# LIH.net
KiCad netlist of a schematic drawn in EAGLE
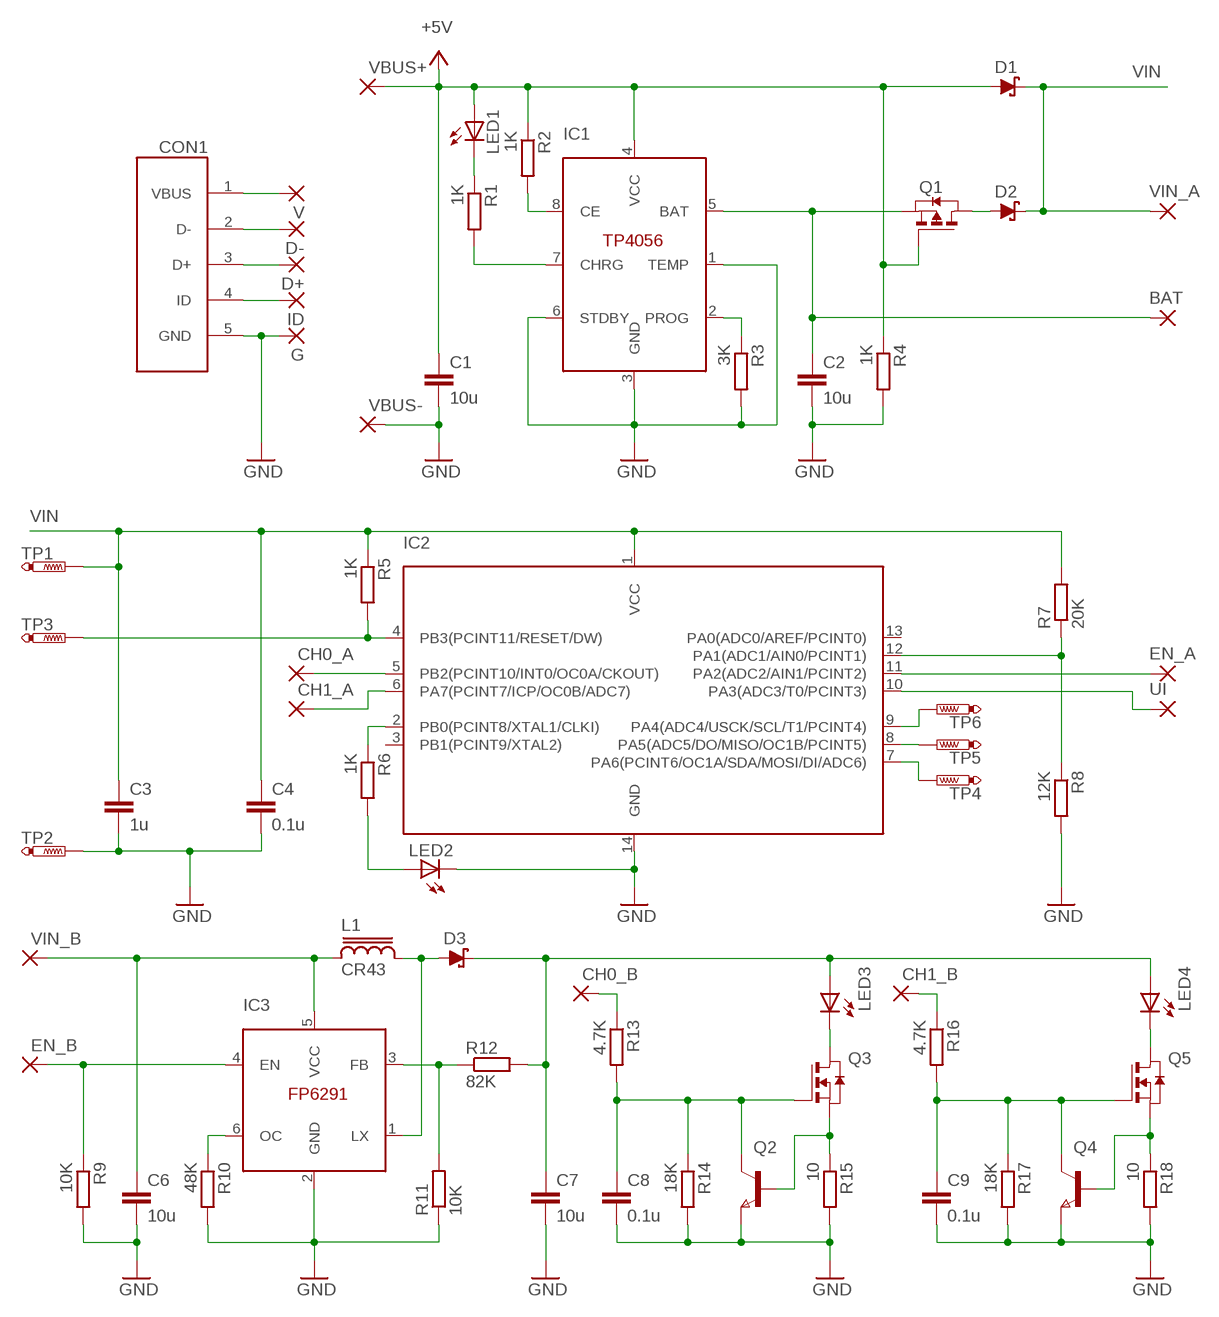
[diagram p0: schematic, sheet 1]

(export (version "E")
  (design (tool "Eeschema 10.0.6"))
  (components
    (comp (ref "BAT")
      (value "WIREPADSMD1,27-254")
      (footprint "eagle-import:1,6_0,8")
      (libsource (lib "eagle-import") (part "1,6/0,8"))
    )
    (comp (ref "C1")
      (value "10u")
      (footprint "eagle-import:C0805K")
      (libsource (lib "eagle-import") (part "C-EUC0805K"))
    )
    (comp (ref "C2")
      (value "10u")
      (footprint "eagle-import:C0805K")
      (libsource (lib "eagle-import") (part "C-EUC0805K"))
    )
    (comp (ref "C3")
      (value "1u")
      (footprint "eagle-import:C0805K")
      (libsource (lib "eagle-import") (part "C-EUC0805K"))
    )
    (comp (ref "C4")
      (value "0.1u")
      (footprint "eagle-import:C0805K")
      (libsource (lib "eagle-import") (part "C-EUC0805K"))
    )
    (comp (ref "C6")
      (value "10u")
      (footprint "eagle-import:C0805K")
      (libsource (lib "eagle-import") (part "C-EUC0805K"))
    )
    (comp (ref "C7")
      (value "10u")
      (footprint "eagle-import:C0805K")
      (libsource (lib "eagle-import") (part "C-EUC0805K"))
    )
    (comp (ref "C8")
      (value "0.1u")
      (footprint "eagle-import:C0805K")
      (libsource (lib "eagle-import") (part "C-EUC0805K"))
    )
    (comp (ref "C9")
      (value "0.1u")
      (footprint "eagle-import:C0805K")
      (libsource (lib "eagle-import") (part "C-EUC0805K"))
    )
    (comp (ref "CH0_A")
      (value "1,6/0,8")
      (footprint "eagle-import:1,6_0,8")
      (libsource (lib "eagle-import") (part "1,6/0,8"))
    )
    (comp (ref "CH0_B")
      (value "1,6/0,8")
      (footprint "eagle-import:1,6_0,8")
      (libsource (lib "eagle-import") (part "1,6/0,8"))
    )
    (comp (ref "CH1_A")
      (value "1,6/0,8")
      (footprint "eagle-import:1,6_0,8")
      (libsource (lib "eagle-import") (part "1,6/0,8"))
    )
    (comp (ref "CH1_B")
      (value "1,6/0,8")
      (footprint "eagle-import:1,6_0,8")
      (libsource (lib "eagle-import") (part "1,6/0,8"))
    )
    (comp (ref "CON1")
      (value "MK5P")
      (footprint "eagle-import:MK5P")
      (libsource (lib "eagle-import") (part "MK5P"))
    )
    (comp (ref "D+")
      (value "SMD2")
      (footprint "eagle-import:SMD1,27-2,54")
      (libsource (lib "eagle-import") (part "SMD2"))
    )
    (comp (ref "D-")
      (value "SMD2")
      (footprint "eagle-import:SMD1,27-2,54")
      (libsource (lib "eagle-import") (part "SMD2"))
    )
    (comp (ref "D1")
      (value "SCHOTTKYSCHOTTKY-DO214AC")
      (footprint "eagle-import:DO214AC")
      (libsource (lib "eagle-import") (part "SCHOTTKYSCHOTTKY-DO214AC"))
    )
    (comp (ref "D2")
      (value "SCHOTTKYSCHOTTKY-DO214AC")
      (footprint "eagle-import:DO214AC")
      (libsource (lib "eagle-import") (part "SCHOTTKYSCHOTTKY-DO214AC"))
    )
    (comp (ref "D3")
      (value "SCHOTTKYSCHOTTKY-DO214AC")
      (footprint "eagle-import:DO214AC")
      (libsource (lib "eagle-import") (part "SCHOTTKYSCHOTTKY-DO214AC"))
    )
    (comp (ref "EN_A")
      (value "WIREPADSMD1,27-254")
      (footprint "eagle-import:1,6_0,8")
      (libsource (lib "eagle-import") (part "1,6/0,8"))
    )
    (comp (ref "EN_B")
      (value "WIREPADSMD1,27-254")
      (footprint "eagle-import:1,6_0,8")
      (libsource (lib "eagle-import") (part "1,6/0,8"))
    )
    (comp (ref "G")
      (value "SMD2")
      (footprint "eagle-import:SMD1,27-2,54")
      (libsource (lib "eagle-import") (part "SMD2"))
    )
    (comp (ref "IC1")
      (value "TP4056")
      (footprint "eagle-import:SO8")
      (libsource (lib "eagle-import") (part "TP4056"))
    )
    (comp (ref "IC2")
      (value "ATTINY24A")
      (footprint "eagle-import:SO14")
      (libsource (lib "eagle-import") (part "ATTINY24A"))
    )
    (comp (ref "IC3")
      (value "FP6291")
      (footprint "eagle-import:SOT-23-6")
      (libsource (lib "eagle-import") (part "FP6291"))
    )
    (comp (ref "ID")
      (value "SMD2")
      (footprint "eagle-import:SMD1,27-2,54")
      (libsource (lib "eagle-import") (part "SMD2"))
    )
    (comp (ref "L1")
      (value "CR43")
      (footprint "eagle-import:CR43")
      (libsource (lib "eagle-import") (part "CR43"))
    )
    (comp (ref "LED1")
      (value "LEDSML0805")
      (footprint "eagle-import:SML0805")
      (libsource (lib "eagle-import") (part "LEDSML0805"))
    )
    (comp (ref "LED2")
      (value "LEDSML0805")
      (footprint "eagle-import:SML0805")
      (libsource (lib "eagle-import") (part "LEDSML0805"))
    )
    (comp (ref "LED3")
      (value "2835")
      (footprint "eagle-import:2835")
      (libsource (lib "eagle-import") (part "2835"))
    )
    (comp (ref "LED4")
      (value "2835")
      (footprint "eagle-import:2835")
      (libsource (lib "eagle-import") (part "2835"))
    )
    (comp (ref "Q1")
      (value "PMOSSOT23")
      (footprint "eagle-import:SOT-23")
      (libsource (lib "eagle-import") (part "PMOSSOT23"))
    )
    (comp (ref "Q2")
      (value "NPNSOT23")
      (footprint "eagle-import:SOT-23")
      (fields (field (name "MPN") "DSS20201L-7"))
      (libsource (lib "eagle-import") (part "NPNSOT23"))
    )
    (comp (ref "Q3")
      (value "NMOSSOT23")
      (footprint "eagle-import:SOT-23")
      (libsource (lib "eagle-import") (part "NMOSSOT23"))
    )
    (comp (ref "Q4")
      (value "NPNSOT23")
      (footprint "eagle-import:SOT-23")
      (fields (field (name "MPN") "DSS20201L-7"))
      (libsource (lib "eagle-import") (part "NPNSOT23"))
    )
    (comp (ref "Q5")
      (value "NMOSSOT23")
      (footprint "eagle-import:SOT-23")
      (libsource (lib "eagle-import") (part "NMOSSOT23"))
    )
    (comp (ref "R1")
      (value "1K")
      (footprint "eagle-import:R0805")
      (libsource (lib "eagle-import") (part "R-EU_R0805"))
    )
    (comp (ref "R2")
      (value "1K")
      (footprint "eagle-import:R0805")
      (libsource (lib "eagle-import") (part "R-EU_R0805"))
    )
    (comp (ref "R3")
      (value "3K")
      (footprint "eagle-import:R0805")
      (libsource (lib "eagle-import") (part "R-EU_R0805"))
    )
    (comp (ref "R4")
      (value "1K")
      (footprint "eagle-import:R0805")
      (libsource (lib "eagle-import") (part "R-EU_R0805"))
    )
    (comp (ref "R5")
      (value "1K")
      (footprint "eagle-import:R0805")
      (libsource (lib "eagle-import") (part "R-EU_R0805"))
    )
    (comp (ref "R6")
      (value "1K")
      (footprint "eagle-import:R0805")
      (libsource (lib "eagle-import") (part "R-EU_R0805"))
    )
    (comp (ref "R7")
      (value "20K")
      (footprint "eagle-import:R0805")
      (libsource (lib "eagle-import") (part "R-EU_R0805"))
    )
    (comp (ref "R8")
      (value "12K")
      (footprint "eagle-import:R0805")
      (libsource (lib "eagle-import") (part "R-EU_R0805"))
    )
    (comp (ref "R9")
      (value "10K")
      (footprint "eagle-import:R0805")
      (libsource (lib "eagle-import") (part "R-EU_R0805"))
    )
    (comp (ref "R10")
      (value "48K")
      (footprint "eagle-import:R0805")
      (libsource (lib "eagle-import") (part "R-EU_R0805"))
    )
    (comp (ref "R11")
      (value "10K")
      (footprint "eagle-import:R0805")
      (libsource (lib "eagle-import") (part "R-EU_R0805"))
    )
    (comp (ref "R12")
      (value "82K")
      (footprint "eagle-import:R0805")
      (libsource (lib "eagle-import") (part "R-EU_R0805"))
    )
    (comp (ref "R13")
      (value "4.7K")
      (footprint "eagle-import:R0805")
      (libsource (lib "eagle-import") (part "R-EU_R0805"))
    )
    (comp (ref "R14")
      (value "18K")
      (footprint "eagle-import:R0805")
      (libsource (lib "eagle-import") (part "R-EU_R0805"))
    )
    (comp (ref "R15")
      (value "10")
      (footprint "eagle-import:R0805")
      (libsource (lib "eagle-import") (part "R-EU_R0805"))
    )
    (comp (ref "R16")
      (value "4.7K")
      (footprint "eagle-import:R0805")
      (libsource (lib "eagle-import") (part "R-EU_R0805"))
    )
    (comp (ref "R17")
      (value "18K")
      (footprint "eagle-import:R0805")
      (libsource (lib "eagle-import") (part "R-EU_R0805"))
    )
    (comp (ref "R18")
      (value "10")
      (footprint "eagle-import:R0805")
      (libsource (lib "eagle-import") (part "R-EU_R0805"))
    )
    (comp (ref "TP1")
      (value "PTR1TP10R")
      (footprint "eagle-import:TP10R")
      (libsource (lib "eagle-import") (part "PTR1TP10R"))
    )
    (comp (ref "TP2")
      (value "PTR1TP10R")
      (footprint "eagle-import:TP10R")
      (libsource (lib "eagle-import") (part "PTR1TP10R"))
    )
    (comp (ref "TP3")
      (value "PTR1TP10R")
      (footprint "eagle-import:TP10R")
      (libsource (lib "eagle-import") (part "PTR1TP10R"))
    )
    (comp (ref "TP4")
      (value "PTR1TP10R")
      (footprint "eagle-import:TP10R")
      (libsource (lib "eagle-import") (part "PTR1TP10R"))
    )
    (comp (ref "TP5")
      (value "PTR1TP10R")
      (footprint "eagle-import:TP10R")
      (libsource (lib "eagle-import") (part "PTR1TP10R"))
    )
    (comp (ref "TP6")
      (value "PTR1TP10R")
      (footprint "eagle-import:TP10R")
      (libsource (lib "eagle-import") (part "PTR1TP10R"))
    )
    (comp (ref "UI")
      (value "WIREPADSMD1,27-254")
      (footprint "eagle-import:1,6_0,8")
      (libsource (lib "eagle-import") (part "1,6/0,8"))
    )
    (comp (ref "V")
      (value "SMD2")
      (footprint "eagle-import:SMD1,27-2,54")
      (libsource (lib "eagle-import") (part "SMD2"))
    )
    (comp (ref "VBUS+")
      (value "WIREPADSMD1,27-254")
      (footprint "eagle-import:1,6_0,8")
      (libsource (lib "eagle-import") (part "1,6/0,8"))
    )
    (comp (ref "VBUS-")
      (value "WIREPADSMD1,27-254")
      (footprint "eagle-import:1,6_0,8")
      (libsource (lib "eagle-import") (part "1,6/0,8"))
    )
    (comp (ref "VIN_A")
      (value "WIREPADSMD1,27-254")
      (footprint "eagle-import:1,6_0,8")
      (libsource (lib "eagle-import") (part "1,6/0,8"))
    )
    (comp (ref "VIN_B")
      (value "WIREPADSMD1,27-254")
      (footprint "eagle-import:1,6_0,8")
      (libsource (lib "eagle-import") (part "1,6/0,8"))
    )
  )
  (nets
    (net (code "1") (name "+5V") (class "Default")
      (node (ref "C1") (pin "1") (pinfunction "1_1") (pintype "passive"))
      (node (ref "D1") (pin "A") (pinfunction "A_A") (pintype "passive"))
      (node (ref "IC1") (pin "4") (pinfunction "VCC_4") (pintype "power_in"))
      (node (ref "LED1") (pin "A") (pinfunction "A_A") (pintype "passive"))
      (node (ref "Q1") (pin "3") (pinfunction "G_3") (pintype "passive"))
      (node (ref "R2") (pin "1") (pinfunction "1_1") (pintype "passive"))
      (node (ref "R4") (pin "1") (pinfunction "1_1") (pintype "passive"))
      (node (ref "VBUS+") (pin "1") (pinfunction "P_1") (pintype "passive"))
    )
    (net (code "2") (name "/VIN") (class "Default")
      (node (ref "C3") (pin "1") (pinfunction "1_1") (pintype "passive"))
      (node (ref "C4") (pin "1") (pinfunction "1_1") (pintype "passive"))
      (node (ref "D1") (pin "C") (pinfunction "C_C") (pintype "passive"))
      (node (ref "D2") (pin "C") (pinfunction "C_C") (pintype "passive"))
      (node (ref "IC2") (pin "1") (pinfunction "VCC_1") (pintype "power_in"))
      (node (ref "R5") (pin "1") (pinfunction "1_1") (pintype "passive"))
      (node (ref "R7") (pin "2") (pinfunction "2_2") (pintype "passive"))
      (node (ref "TP1") (pin "TP") (pinfunction "TP_TP") (pintype "input"))
      (node (ref "VIN_A") (pin "1") (pinfunction "P_1") (pintype "passive"))
    )
    (net (code "3") (name "GND") (class "Default")
      (node (ref "C1") (pin "2") (pinfunction "2_2") (pintype "passive"))
      (node (ref "C2") (pin "2") (pinfunction "2_2") (pintype "passive"))
      (node (ref "C3") (pin "2") (pinfunction "2_2") (pintype "passive"))
      (node (ref "C4") (pin "2") (pinfunction "2_2") (pintype "passive"))
      (node (ref "C6") (pin "2") (pinfunction "2_2") (pintype "passive"))
      (node (ref "C7") (pin "2") (pinfunction "2_2") (pintype "passive"))
      (node (ref "C8") (pin "2") (pinfunction "2_2") (pintype "passive"))
      (node (ref "C9") (pin "2") (pinfunction "2_2") (pintype "passive"))
      (node (ref "CON1") (pin "5") (pinfunction "GND_5") (pintype "bidirectional"))
      (node (ref "G") (pin "1") (pinfunction "P_1") (pintype "passive"))
      (node (ref "IC1") (pin "1") (pinfunction "TEMP_1") (pintype "passive"))
      (node (ref "IC1") (pin "3") (pinfunction "GND_3") (pintype "power_in"))
      (node (ref "IC1") (pin "6") (pinfunction "STDBY_6") (pintype "passive"))
      (node (ref "IC2") (pin "14") (pinfunction "GND_14") (pintype "power_in"))
      (node (ref "IC3") (pin "2") (pinfunction "GND_2") (pintype "power_in"))
      (node (ref "LED2") (pin "C") (pinfunction "C_C") (pintype "passive"))
      (node (ref "Q2") (pin "2") (pinfunction "E_2") (pintype "passive"))
      (node (ref "Q4") (pin "2") (pinfunction "E_2") (pintype "passive"))
      (node (ref "R10") (pin "2") (pinfunction "2_2") (pintype "passive"))
      (node (ref "R11") (pin "1") (pinfunction "1_1") (pintype "passive"))
      (node (ref "R14") (pin "2") (pinfunction "2_2") (pintype "passive"))
      (node (ref "R15") (pin "2") (pinfunction "2_2") (pintype "passive"))
      (node (ref "R17") (pin "2") (pinfunction "2_2") (pintype "passive"))
      (node (ref "R18") (pin "2") (pinfunction "2_2") (pintype "passive"))
      (node (ref "R3") (pin "2") (pinfunction "2_2") (pintype "passive"))
      (node (ref "R4") (pin "2") (pinfunction "2_2") (pintype "passive"))
      (node (ref "R8") (pin "2") (pinfunction "2_2") (pintype "passive"))
      (node (ref "R9") (pin "2") (pinfunction "2_2") (pintype "passive"))
      (node (ref "TP2") (pin "TP") (pinfunction "TP_TP") (pintype "input"))
      (node (ref "VBUS-") (pin "1") (pinfunction "P_1") (pintype "passive"))
    )
    (net (code "4") (name "Net-(BAT-P)") (class "Default")
      (node (ref "BAT") (pin "1") (pinfunction "P_1") (pintype "passive"))
      (node (ref "C2") (pin "1") (pinfunction "1_1") (pintype "passive"))
      (node (ref "IC1") (pin "5") (pinfunction "BAT_5") (pintype "passive"))
      (node (ref "Q1") (pin "2") (pinfunction "S_2") (pintype "passive"))
    )
    (net (code "5") (name "Net-(CH0_A-P)") (class "Default")
      (node (ref "CH0_A") (pin "1") (pinfunction "P_1") (pintype "passive"))
      (node (ref "IC2") (pin "5") (pinfunction "PB2(PCINT10/INT0/OC0A/CKOUT)_5") (pintype "passive"))
    )
    (net (code "6") (name "Net-(CH0_B-P)") (class "Default")
      (node (ref "CH0_B") (pin "1") (pinfunction "P_1") (pintype "passive"))
      (node (ref "R13") (pin "1") (pinfunction "1_1") (pintype "passive"))
    )
    (net (code "7") (name "Net-(CH1_A-P)") (class "Default")
      (node (ref "CH1_A") (pin "1") (pinfunction "P_1") (pintype "passive"))
      (node (ref "IC2") (pin "6") (pinfunction "PA7(PCINT7/ICP/OC0B/ADC7)_6") (pintype "passive"))
    )
    (net (code "8") (name "Net-(CH1_B-P)") (class "Default")
      (node (ref "CH1_B") (pin "1") (pinfunction "P_1") (pintype "passive"))
      (node (ref "R16") (pin "1") (pinfunction "1_1") (pintype "passive"))
    )
    (net (code "9") (name "Net-(CON1-D+)") (class "Default")
      (node (ref "CON1") (pin "3") (pinfunction "D+_3") (pintype "bidirectional"))
      (node (ref "D+") (pin "1") (pinfunction "P_1") (pintype "passive"))
    )
    (net (code "10") (name "Net-(CON1-D-)") (class "Default")
      (node (ref "CON1") (pin "2") (pinfunction "D-_2") (pintype "bidirectional"))
      (node (ref "D-") (pin "1") (pinfunction "P_1") (pintype "passive"))
    )
    (net (code "11") (name "Net-(CON1-ID)") (class "Default")
      (node (ref "CON1") (pin "4") (pinfunction "ID_4") (pintype "bidirectional"))
      (node (ref "ID") (pin "1") (pinfunction "P_1") (pintype "passive"))
    )
    (net (code "12") (name "Net-(CON1-VBUS)") (class "Default")
      (node (ref "CON1") (pin "1") (pinfunction "VBUS_1") (pintype "bidirectional"))
      (node (ref "V") (pin "1") (pinfunction "P_1") (pintype "passive"))
    )
    (net (code "13") (name "Net-(EN_A-P)") (class "Default")
      (node (ref "EN_A") (pin "1") (pinfunction "P_1") (pintype "passive"))
      (node (ref "IC2") (pin "11") (pinfunction "PA2(ADC2/AIN1/PCINT2)_11") (pintype "passive"))
    )
    (net (code "14") (name "Net-(EN_B-P)") (class "Default")
      (node (ref "EN_B") (pin "1") (pinfunction "P_1") (pintype "passive"))
      (node (ref "IC3") (pin "4") (pinfunction "EN_4") (pintype "passive"))
      (node (ref "R9") (pin "1") (pinfunction "1_1") (pintype "passive"))
    )
    (net (code "15") (name "Net-(IC1-CE)") (class "Default")
      (node (ref "IC1") (pin "8") (pinfunction "CE_8") (pintype "passive"))
      (node (ref "R2") (pin "2") (pinfunction "2_2") (pintype "passive"))
    )
    (net (code "16") (name "Net-(IC1-CHRG)") (class "Default")
      (node (ref "IC1") (pin "7") (pinfunction "CHRG_7") (pintype "passive"))
      (node (ref "R1") (pin "2") (pinfunction "2_2") (pintype "passive"))
    )
    (net (code "17") (name "Net-(IC1-PROG)") (class "Default")
      (node (ref "IC1") (pin "2") (pinfunction "PROG_2") (pintype "passive"))
      (node (ref "R3") (pin "1") (pinfunction "1_1") (pintype "passive"))
    )
    (net (code "18") (name "Net-(IC2-PA1(ADC1{slash}AIN0{slash}PCINT1))") (class "Default")
      (node (ref "IC2") (pin "12") (pinfunction "PA1(ADC1/AIN0/PCINT1)_12") (pintype "passive"))
      (node (ref "R7") (pin "1") (pinfunction "1_1") (pintype "passive"))
      (node (ref "R8") (pin "1") (pinfunction "1_1") (pintype "passive"))
    )
    (net (code "19") (name "Net-(IC2-PA3(ADC3{slash}T0{slash}PCINT3))") (class "Default")
      (node (ref "IC2") (pin "10") (pinfunction "PA3(ADC3/T0/PCINT3)_10") (pintype "passive"))
      (node (ref "UI") (pin "1") (pinfunction "P_1") (pintype "passive"))
    )
    (net (code "20") (name "Net-(IC2-PA4(ADC4{slash}USCK{slash}SCL{slash}T1{slash}PCINT4))") (class "Default")
      (node (ref "IC2") (pin "9") (pinfunction "PA4(ADC4/USCK/SCL/T1/PCINT4)_9") (pintype "passive"))
      (node (ref "TP6") (pin "TP") (pinfunction "TP_TP") (pintype "input"))
    )
    (net (code "21") (name "Net-(IC2-PA5(ADC5{slash}DO{slash}MISO{slash}OC1B{slash}PCINT5))") (class "Default")
      (node (ref "IC2") (pin "8") (pinfunction "PA5(ADC5/DO/MISO/OC1B/PCINT5)_8") (pintype "passive"))
      (node (ref "TP5") (pin "TP") (pinfunction "TP_TP") (pintype "input"))
    )
    (net (code "22") (name "Net-(IC2-PA6(PCINT6{slash}OC1A{slash}SDA{slash}MOSI{slash}DI{slash}ADC6))") (class "Default")
      (node (ref "IC2") (pin "7") (pinfunction "PA6(PCINT6/OC1A/SDA/MOSI/DI/ADC6)_7") (pintype "passive"))
      (node (ref "TP4") (pin "TP") (pinfunction "TP_TP") (pintype "input"))
    )
    (net (code "23") (name "Net-(IC2-PB0(PCINT8{slash}XTAL1{slash}CLKI))") (class "Default")
      (node (ref "IC2") (pin "2") (pinfunction "PB0(PCINT8/XTAL1/CLKI)_2") (pintype "passive"))
      (node (ref "R6") (pin "1") (pinfunction "1_1") (pintype "passive"))
    )
    (net (code "24") (name "Net-(IC2-PB3(PCINT11{slash}RESET{slash}DW))") (class "Default")
      (node (ref "IC2") (pin "4") (pinfunction "PB3(PCINT11/RESET/DW)_4") (pintype "passive"))
      (node (ref "R5") (pin "2") (pinfunction "2_2") (pintype "passive"))
      (node (ref "TP3") (pin "TP") (pinfunction "TP_TP") (pintype "input"))
    )
    (net (code "25") (name "Net-(IC3-FB)") (class "Default")
      (node (ref "IC3") (pin "3") (pinfunction "FB_3") (pintype "passive"))
      (node (ref "R11") (pin "2") (pinfunction "2_2") (pintype "passive"))
      (node (ref "R12") (pin "1") (pinfunction "1_1") (pintype "passive"))
    )
    (net (code "26") (name "Net-(IC3-LX)") (class "Default")
      (node (ref "D3") (pin "A") (pinfunction "A_A") (pintype "passive"))
      (node (ref "IC3") (pin "1") (pinfunction "LX_1") (pintype "passive"))
      (node (ref "L1") (pin "2") (pinfunction "2_2") (pintype "passive"))
    )
    (net (code "27") (name "Net-(IC3-OC)") (class "Default")
      (node (ref "IC3") (pin "6") (pinfunction "OC_6") (pintype "passive"))
      (node (ref "R10") (pin "1") (pinfunction "1_1") (pintype "passive"))
    )
    (net (code "28") (name "Net-(IC3-VCC)") (class "Default")
      (node (ref "C6") (pin "1") (pinfunction "1_1") (pintype "passive"))
      (node (ref "IC3") (pin "5") (pinfunction "VCC_5") (pintype "power_in"))
      (node (ref "L1") (pin "1") (pinfunction "1_1") (pintype "passive"))
      (node (ref "VIN_B") (pin "1") (pinfunction "P_1") (pintype "passive"))
    )
    (net (code "29") (name "Net-(LED1-PadC)") (class "Default")
      (node (ref "LED1") (pin "C") (pinfunction "C_C") (pintype "passive"))
      (node (ref "R1") (pin "1") (pinfunction "1_1") (pintype "passive"))
    )
    (net (code "30") (name "Net-(LED2-PadA)") (class "Default")
      (node (ref "LED2") (pin "A") (pinfunction "A_A") (pintype "passive"))
      (node (ref "R6") (pin "2") (pinfunction "2_2") (pintype "passive"))
    )
    (net (code "31") (name "Net-(LED3-A)") (class "Default")
      (node (ref "C7") (pin "1") (pinfunction "1_1") (pintype "passive"))
      (node (ref "D3") (pin "C") (pinfunction "C_C") (pintype "passive"))
      (node (ref "LED3") (pin "1") (pinfunction "A_1") (pintype "passive"))
      (node (ref "LED4") (pin "1") (pinfunction "A_1") (pintype "passive"))
      (node (ref "R12") (pin "2") (pinfunction "2_2") (pintype "passive"))
    )
    (net (code "32") (name "Net-(LED3-C)") (class "Default")
      (node (ref "LED3") (pin "2") (pinfunction "C_2") (pintype "passive"))
      (node (ref "Q3") (pin "1") (pinfunction "D_1") (pintype "passive"))
    )
    (net (code "33") (name "Net-(LED4-C)") (class "Default")
      (node (ref "LED4") (pin "2") (pinfunction "C_2") (pintype "passive"))
      (node (ref "Q5") (pin "1") (pinfunction "D_1") (pintype "passive"))
    )
    (net (code "34") (name "Net-(Q1-D)") (class "Default")
      (node (ref "D2") (pin "A") (pinfunction "A_A") (pintype "passive"))
      (node (ref "Q1") (pin "1") (pinfunction "D_1") (pintype "passive"))
    )
    (net (code "35") (name "Net-(Q2-B)") (class "Default")
      (node (ref "Q2") (pin "3") (pinfunction "B_3") (pintype "passive"))
      (node (ref "Q3") (pin "2") (pinfunction "S_2") (pintype "passive"))
      (node (ref "R15") (pin "1") (pinfunction "1_1") (pintype "passive"))
    )
    (net (code "36") (name "Net-(Q2-C)") (class "Default")
      (node (ref "C8") (pin "1") (pinfunction "1_1") (pintype "passive"))
      (node (ref "Q2") (pin "1") (pinfunction "C_1") (pintype "passive"))
      (node (ref "Q3") (pin "3") (pinfunction "G_3") (pintype "passive"))
      (node (ref "R13") (pin "2") (pinfunction "2_2") (pintype "passive"))
      (node (ref "R14") (pin "1") (pinfunction "1_1") (pintype "passive"))
    )
    (net (code "37") (name "Net-(Q4-B)") (class "Default")
      (node (ref "Q4") (pin "3") (pinfunction "B_3") (pintype "passive"))
      (node (ref "Q5") (pin "2") (pinfunction "S_2") (pintype "passive"))
      (node (ref "R18") (pin "1") (pinfunction "1_1") (pintype "passive"))
    )
    (net (code "38") (name "Net-(Q4-C)") (class "Default")
      (node (ref "C9") (pin "1") (pinfunction "1_1") (pintype "passive"))
      (node (ref "Q4") (pin "1") (pinfunction "C_1") (pintype "passive"))
      (node (ref "Q5") (pin "3") (pinfunction "G_3") (pintype "passive"))
      (node (ref "R16") (pin "2") (pinfunction "2_2") (pintype "passive"))
      (node (ref "R17") (pin "1") (pinfunction "1_1") (pintype "passive"))
    )
    (net (code "39") (name "unconnected-(IC2-PA0(ADC0{slash}AREF{slash}PCINT0)-Pad13)") (class "Default")
      (node (ref "IC2") (pin "13") (pinfunction "PA0(ADC0/AREF/PCINT0)_13") (pintype "passive"))
    )
    (net (code "40") (name "unconnected-(IC2-PB1(PCINT9{slash}XTAL2)-Pad3)") (class "Default")
      (node (ref "IC2") (pin "3") (pinfunction "PB1(PCINT9/XTAL2)_3") (pintype "passive"))
    )
  )
)
